# AlephFDRv100a.net
KiCad netlist of a schematic drawn in EAGLE
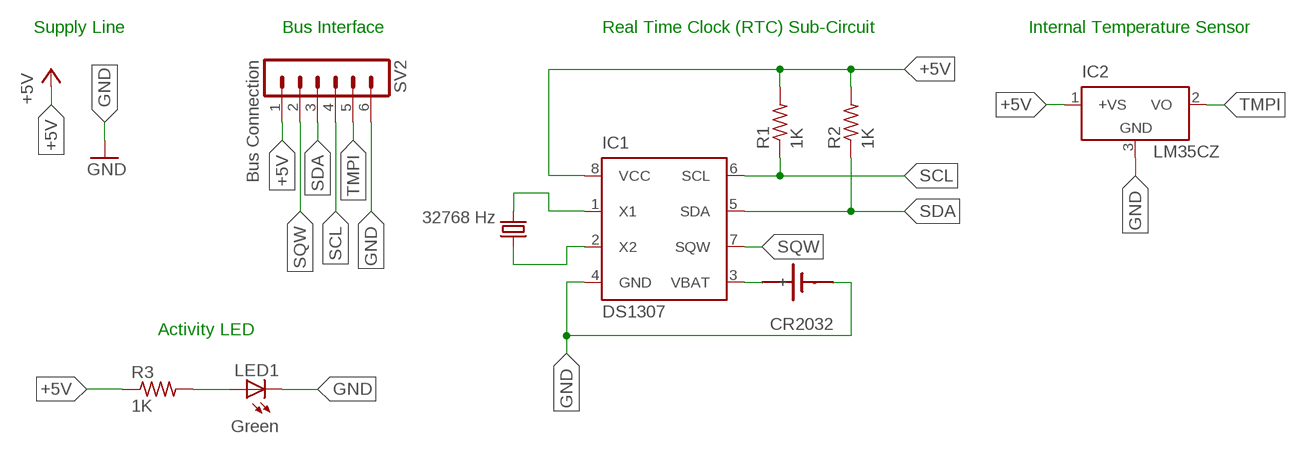
[diagram p0: schematic, sheet 1]

(export (version "E")
  (design (tool "Eeschema 10.0.6"))
  (components
    (comp (ref "BAT1")
      (value "CR2032")
      (footprint "eagle-import:SN2032")
      (libsource (lib "eagle-import") (part "SN2032"))
    )
    (comp (ref "IC1")
      (value "DS1307")
      (footprint "eagle-import:DIL08")
      (libsource (lib "eagle-import") (part "DS1307"))
    )
    (comp (ref "IC2")
      (value "LM35CZ")
      (footprint "eagle-import:TO92")
      (libsource (lib "eagle-import") (part "LM35CZ"))
    )
    (comp (ref "LED1")
      (value "Green")
      (footprint "eagle-import:LED3MM")
      (libsource (lib "eagle-import") (part "LED3MM"))
    )
    (comp (ref "Q1")
      (value "32768 Hz")
      (footprint "eagle-import:TC26H")
      (libsource (lib "eagle-import") (part "CRYSTALTC26H"))
    )
    (comp (ref "R1")
      (value "1K")
      (footprint "eagle-import:0207_10")
      (libsource (lib "eagle-import") (part "R-US_0207/10"))
    )
    (comp (ref "R2")
      (value "1K")
      (footprint "eagle-import:0207_10")
      (libsource (lib "eagle-import") (part "R-US_0207/10"))
    )
    (comp (ref "R3")
      (value "1K")
      (footprint "eagle-import:0207_10")
      (libsource (lib "eagle-import") (part "R-US_0207/10"))
    )
    (comp (ref "SV2")
      (value "Bus Connection")
      (footprint "eagle-import:MA06-1")
      (libsource (lib "eagle-import") (part "MA06-1"))
    )
  )
  (nets
    (net (code "1") (name "+5V") (class "Default")
      (node (ref "IC1") (pin "8") (pinfunction "VCC_8") (pintype "power_in"))
      (node (ref "IC2") (pin "1") (pinfunction "+VS_1") (pintype "input"))
      (node (ref "R1") (pin "2") (pinfunction "2_2") (pintype "passive"))
      (node (ref "R2") (pin "2") (pinfunction "2_2") (pintype "passive"))
      (node (ref "R3") (pin "1") (pinfunction "1_1") (pintype "passive"))
      (node (ref "SV2") (pin "1") (pinfunction "1_1") (pintype "passive"))
    )
    (net (code "2") (name "GND") (class "Default")
      (node (ref "BAT1") (pin "-") (pinfunction "-_-") (pintype "passive"))
      (node (ref "IC1") (pin "4") (pinfunction "GND_4") (pintype "power_in"))
      (node (ref "IC2") (pin "3") (pinfunction "GND_3") (pintype "power_in"))
      (node (ref "LED1") (pin "K") (pinfunction "C_K") (pintype "passive"))
      (node (ref "SV2") (pin "6") (pinfunction "6_6") (pintype "passive"))
    )
    (net (code "3") (name "Net-(IC1-VBAT)") (class "Default")
      (node (ref "BAT1") (pin "+") (pinfunction "+_+") (pintype "passive"))
      (node (ref "IC1") (pin "3") (pinfunction "VBAT_3") (pintype "passive"))
    )
    (net (code "4") (name "Net-(IC1-X1)") (class "Default")
      (node (ref "IC1") (pin "1") (pinfunction "X1_1") (pintype "input"))
      (node (ref "Q1") (pin "2") (pinfunction "2_2") (pintype "passive"))
    )
    (net (code "5") (name "Net-(IC1-X2)") (class "Default")
      (node (ref "IC1") (pin "2") (pinfunction "X2_2") (pintype "output"))
      (node (ref "Q1") (pin "1") (pinfunction "1_1") (pintype "passive"))
    )
    (net (code "6") (name "Net-(LED1-PadA)") (class "Default")
      (node (ref "LED1") (pin "A") (pinfunction "A_A") (pintype "passive"))
      (node (ref "R3") (pin "2") (pinfunction "2_2") (pintype "passive"))
    )
    (net (code "7") (name "SCL") (class "Default")
      (node (ref "IC1") (pin "6") (pinfunction "SCL_6") (pintype "input"))
      (node (ref "R1") (pin "1") (pinfunction "1_1") (pintype "passive"))
      (node (ref "SV2") (pin "4") (pinfunction "4_4") (pintype "passive"))
    )
    (net (code "8") (name "SDA") (class "Default")
      (node (ref "IC1") (pin "5") (pinfunction "SDA_5") (pintype "bidirectional"))
      (node (ref "R2") (pin "1") (pinfunction "1_1") (pintype "passive"))
      (node (ref "SV2") (pin "3") (pinfunction "3_3") (pintype "passive"))
    )
    (net (code "9") (name "SQW") (class "Default")
      (node (ref "IC1") (pin "7") (pinfunction "SQW_7") (pintype "open_collector"))
      (node (ref "SV2") (pin "2") (pinfunction "2_2") (pintype "passive"))
    )
    (net (code "10") (name "TMPI") (class "Default")
      (node (ref "IC2") (pin "2") (pinfunction "VO_2") (pintype "input"))
      (node (ref "SV2") (pin "5") (pinfunction "5_5") (pintype "passive"))
    )
  )
)
